# Main.net
KiCad netlist of a schematic drawn in Altium Designer
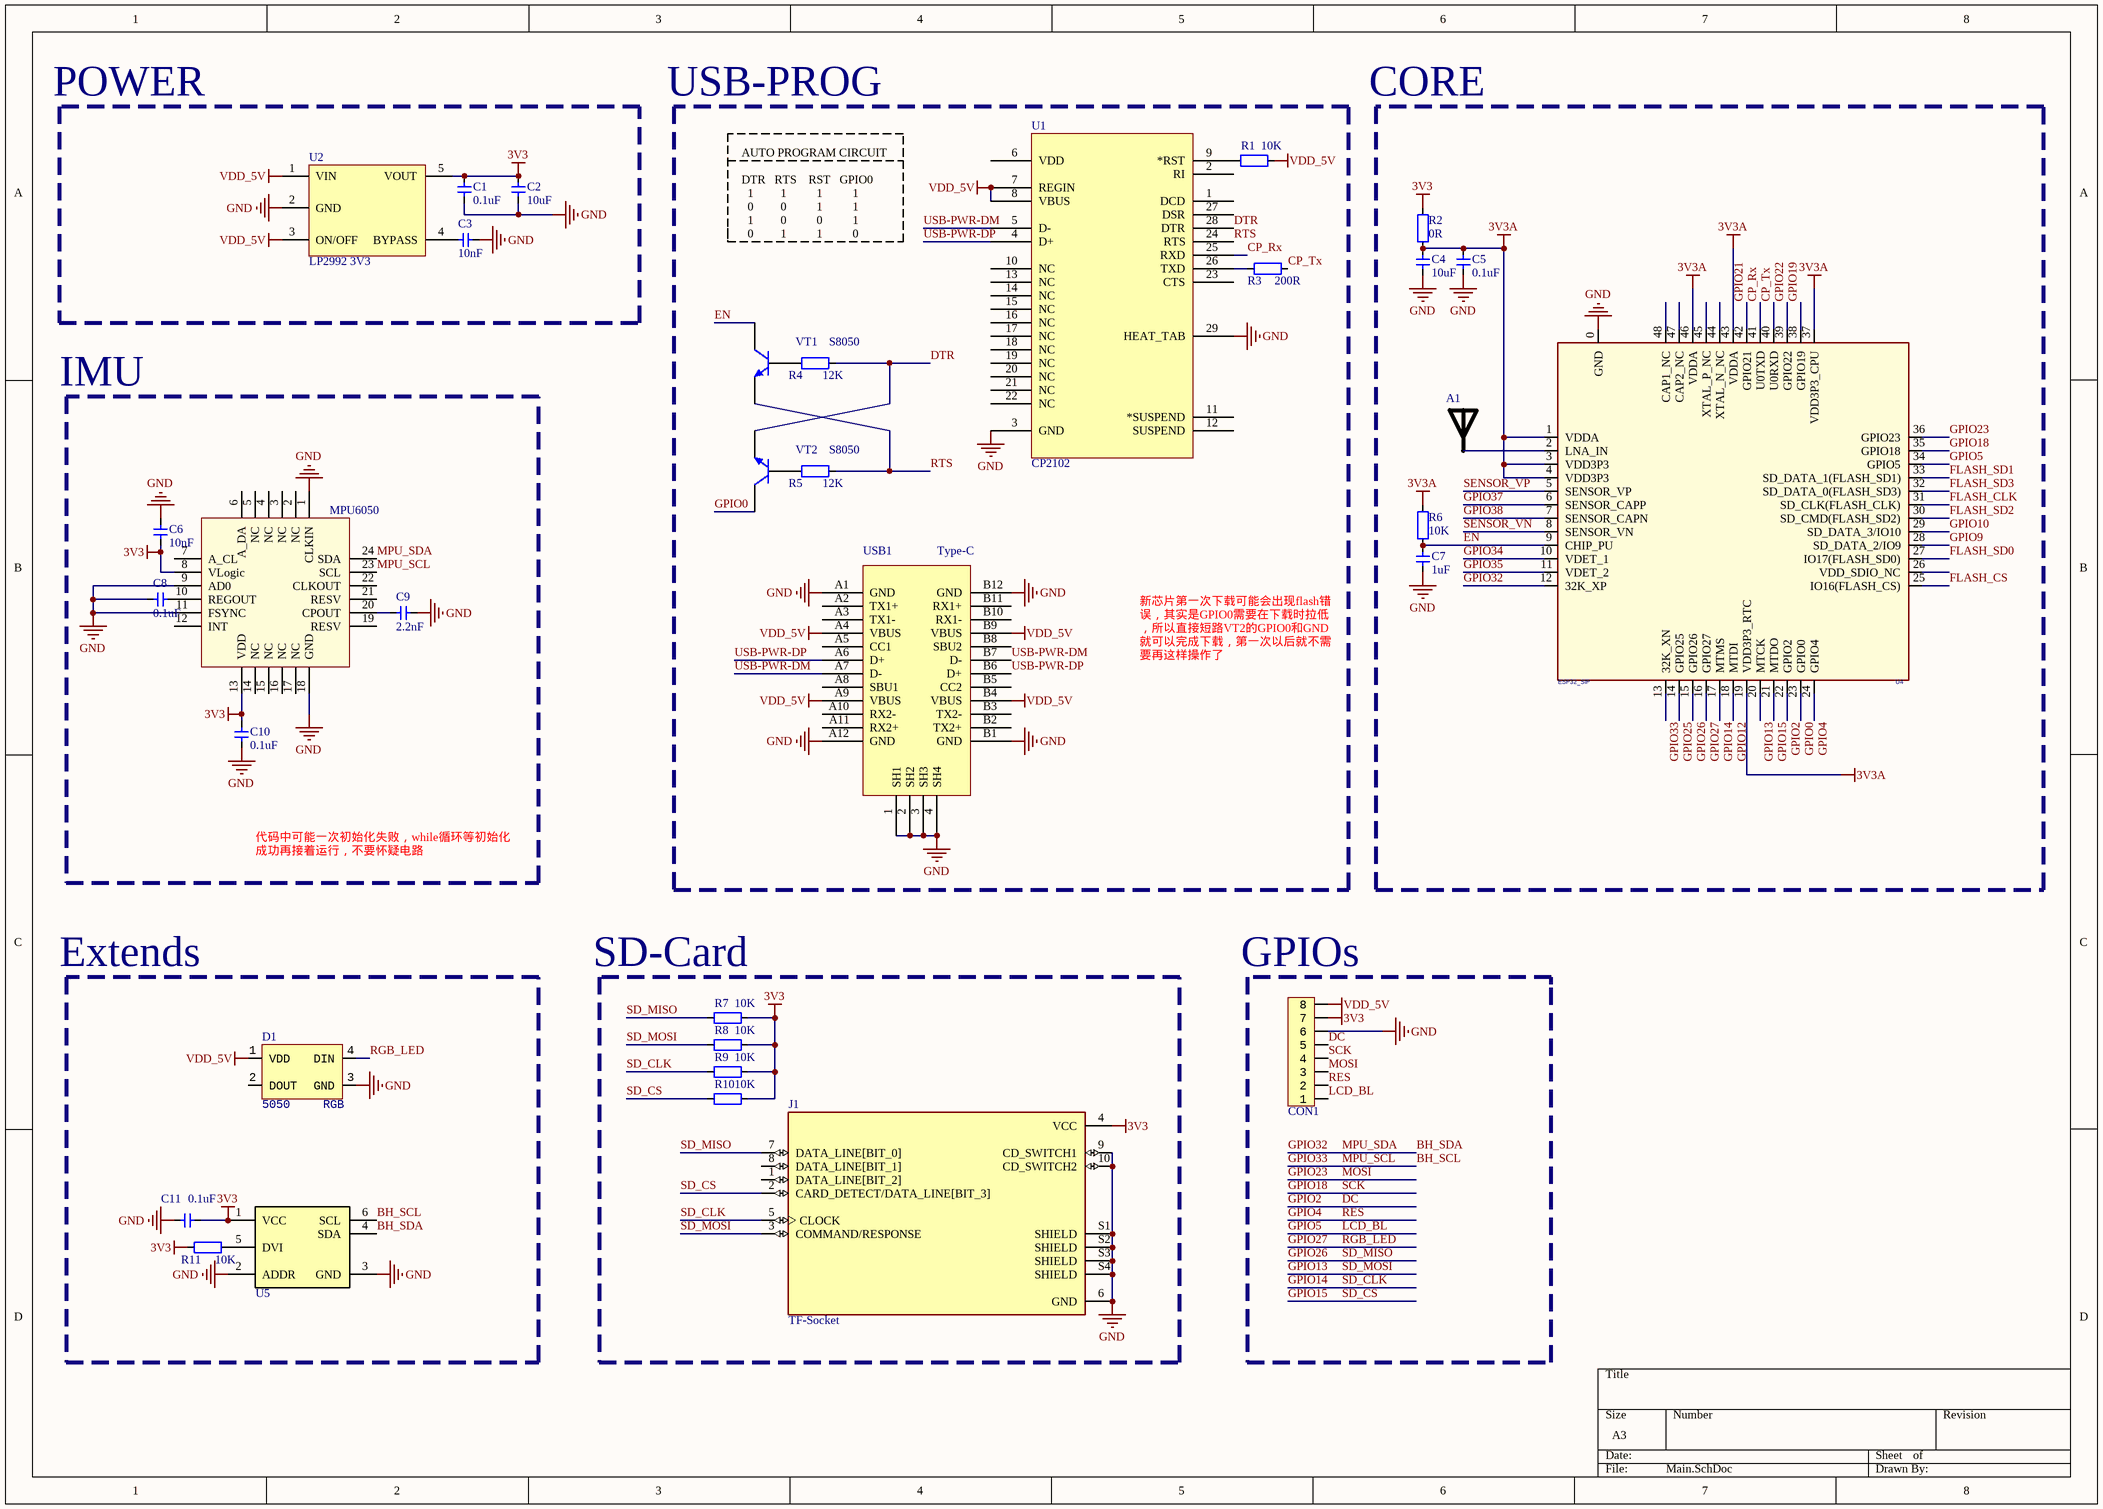
[diagram p0: Main.SchDoc]

(export (version "E")
  (design (tool "Eeschema 10.0.6"))
  (components
    (comp (ref "A1")
      (value "RAINSUN")
      (footprint "ANT-Rainsun-AN5120")
      (libsource (lib "MyPcbLib") (part "ANT-Rainsun-AP5120"))
    )
    (comp (ref "C1")
      (value "0.1uF")
      (footprint "CAP_0402")
      (description "Capacitor")
      (libsource (lib "MyPcbLib") (part "电容-0402"))
    )
    (comp (ref "C2")
      (value "10uF")
      (footprint "CAP_0402")
      (description "Capacitor")
      (libsource (lib "MyPcbLib") (part "电容-0402"))
    )
    (comp (ref "C3")
      (value "10nF")
      (footprint "CAP_0402")
      (description "Capacitor")
      (libsource (lib "MyPcbLib") (part "电容-0402"))
    )
    (comp (ref "C4")
      (value "10uF")
      (footprint "CAP_0402")
      (description "Capacitor")
      (libsource (lib "MyPcbLib") (part "电容-0402"))
    )
    (comp (ref "C5")
      (value "0.1uF")
      (footprint "CAP_0402")
      (description "Capacitor")
      (libsource (lib "MyPcbLib") (part "电容-0402"))
    )
    (comp (ref "C6")
      (value "10nF")
      (footprint "CAP_0402")
      (description "Capacitor")
      (libsource (lib "MyPcbLib") (part "电容-0402"))
    )
    (comp (ref "C7")
      (value "1uF")
      (footprint "CAP_0402")
      (description "Capacitor")
      (libsource (lib "MyPcbLib") (part "电容-0402"))
    )
    (comp (ref "C8")
      (value "0.1uF")
      (footprint "CAP_0402")
      (description "Capacitor")
      (libsource (lib "MyPcbLib") (part "电容-0402"))
    )
    (comp (ref "C9")
      (value "2.2nF")
      (footprint "CAP_0402")
      (description "Capacitor")
      (libsource (lib "MyPcbLib") (part "电容-0402"))
    )
    (comp (ref "C10")
      (value "0.1uF")
      (footprint "CAP_0402")
      (description "Capacitor")
      (libsource (lib "MyPcbLib") (part "电容-0402"))
    )
    (comp (ref "C11")
      (value "0.1uF")
      (footprint "CAP_0402")
      (description "Capacitor")
      (libsource (lib "MyPcbLib") (part "电容-0402"))
    )
    (comp (ref "CON1")
      (value "FFC_0.5_8")
      (footprint "FFC_0.5_8")
      (description "FFC")
      (libsource (lib "KitSprout") (part "FFC_0.5_8"))
    )
    (comp (ref "D1")
      (value "RGB")
      (footprint "LED_5050_WS2812B")
      (description "LED")
      (fields (field (name "TYPE") "5050"))
      (libsource (lib "KitSprout") (part "LED_5050_WS2812B"))
    )
    (comp (ref "J1")
      (value "TF-Socket")
      (footprint "TF-Card-Amphenol with TF")
      (description "10 _8 + 2_ Position Card Connector Secure Digital - microSDâ„¢ Surface Mount, Right Angle Gold")
      (fields (field (name "MP") "1140084168") (field (name "MF") "Amphenol Commercial Products"))
      (libsource (lib "MyPcbLib") (part "TF-Socket"))
    )
    (comp (ref "R1")
      (value "10K")
      (footprint "RES_0402")
      (description "Resistor")
      (libsource (lib "") (part "电阻-0402_1"))
    )
    (comp (ref "R2")
      (value "0R")
      (footprint "RES_0402")
      (description "Resistor")
      (libsource (lib "MyPcbLib") (part "电阻-0402"))
    )
    (comp (ref "R3")
      (value "200R")
      (footprint "RES_0402")
      (description "Resistor")
      (libsource (lib "") (part "电阻-0402_1"))
    )
    (comp (ref "R4")
      (value "12K")
      (footprint "RES_0402")
      (description "Resistor")
      (libsource (lib "") (part "电阻-0402_1"))
    )
    (comp (ref "R5")
      (value "12K")
      (footprint "RES_0402")
      (description "Resistor")
      (libsource (lib "") (part "电阻-0402_1"))
    )
    (comp (ref "R6")
      (value "10K")
      (footprint "RES_0402")
      (description "Resistor")
      (libsource (lib "MyPcbLib") (part "电阻-0402"))
    )
    (comp (ref "R7")
      (value "10K")
      (footprint "RES_0402")
      (description "Resistor")
      (libsource (lib "") (part "电阻-0402_1"))
    )
    (comp (ref "R8")
      (value "10K")
      (footprint "RES_0402")
      (description "Resistor")
      (libsource (lib "") (part "电阻-0402_1"))
    )
    (comp (ref "R9")
      (value "10K")
      (footprint "RES_0402")
      (description "Resistor")
      (libsource (lib "") (part "电阻-0402_1"))
    )
    (comp (ref "R10")
      (value "10K")
      (footprint "RES_0402")
      (description "Resistor")
      (libsource (lib "") (part "电阻-0402_1"))
    )
    (comp (ref "R11")
      (value "10K")
      (footprint "RES_0402")
      (description "Resistor")
      (libsource (lib "") (part "电阻-0402_1"))
    )
    (comp (ref "U1")
      (value "CP2102")
      (footprint "QFN-28")
      (description "USB转TTL")
      (libsource (lib "mLib") (part "CP2102"))
    )
    (comp (ref "U2")
      (value "LP2992 3V3")
      (footprint "SOT23-5")
      (description "LDO")
      (libsource (lib "MyPcbLib") (part "LP2992"))
    )
    (comp (ref "U3")
      (value "MPU6050")
      (footprint "QFN-24")
      (description "六轴传感器")
      (libsource (lib "mLib") (part "MPU6050"))
    )
    (comp (ref "U4")
      (value "ESP32_SIP")
      (footprint "QFN-48_7X7")
      (libsource (lib "MyPcbLib") (part "ESP32-PICO"))
    )
    (comp (ref "U5")
      (value "BH1750FVI-TR")
      (footprint "BH1750FVI")
      (libsource (lib "MyPcbLib") (part "BH1750FVI-TR"))
    )
    (comp (ref "USB1")
      (value "Type-C")
      (footprint "Type-C-TOP")
      (libsource (lib "MyPcbLib") (part "USB-Type-C-TOP"))
    )
    (comp (ref "VT1")
      (value "S8050")
      (footprint "SMT_TRIODE_NPN")
      (description "Surface mount NPN transistor, package SOT-23")
      (libsource (lib "MyPcbLib") (part "SMT_TRIODE_NPN"))
    )
    (comp (ref "VT2")
      (value "S8050")
      (footprint "SMT_TRIODE_NPN")
      (description "Surface mount NPN transistor, package SOT-23")
      (libsource (lib "MyPcbLib") (part "SMT_TRIODE_NPN"))
    )
  )
  (nets
    (net (code "1") (name "/BH_SCL") (class "Default")
      (node (ref "U3") (pin "23") (pinfunction "SCL_23") (pintype "passive"))
      (node (ref "U4") (pin "13") (pinfunction "32K_XN_13") (pintype "passive"))
      (node (ref "U5") (pin "6") (pinfunction "SCL_6") (pintype "passive"))
    )
    (net (code "2") (name "/BH_SDA") (class "Default")
      (node (ref "U3") (pin "24") (pinfunction "SDA_24") (pintype "passive"))
      (node (ref "U4") (pin "12") (pinfunction "32K_XP_12") (pintype "passive"))
      (node (ref "U5") (pin "4") (pinfunction "SDA_4") (pintype "passive"))
    )
    (net (code "3") (name "/CP_Rx") (class "Default")
      (node (ref "U1") (pin "25") (pinfunction "RXD_25") (pintype "passive"))
      (node (ref "U4") (pin "41") (pinfunction "U0TXD_41") (pintype "power_in"))
    )
    (net (code "4") (name "/CP_Tx") (class "Default")
      (node (ref "R3") (pin "1") (pinfunction "1_1") (pintype "passive"))
      (node (ref "U4") (pin "40") (pinfunction "U0RXD_40") (pintype "power_in"))
    )
    (net (code "5") (name "/DC") (class "Default")
      (node (ref "CON1") (pin "5") (pinfunction "5_5") (pintype "passive"))
      (node (ref "U4") (pin "22") (pinfunction "GPIO2_22") (pintype "passive"))
    )
    (net (code "6") (name "/DTR") (class "Default")
      (node (ref "R4") (pin "1") (pinfunction "1_1") (pintype "passive"))
      (node (ref "U1") (pin "28") (pinfunction "DTR_28") (pintype "passive"))
      (node (ref "VT2") (pin "2") (pinfunction "E_2") (pintype "passive"))
    )
    (net (code "7") (name "/EN") (class "Default")
      (node (ref "C7") (pin "1") (pinfunction "1_1") (pintype "passive"))
      (node (ref "R6") (pin "2") (pinfunction "2_2") (pintype "passive"))
      (node (ref "U4") (pin "9") (pinfunction "CHIP_PU_9") (pintype "passive"))
      (node (ref "VT1") (pin "3") (pinfunction "C_3") (pintype "passive"))
    )
    (net (code "8") (name "/FLASH_CLK") (class "Default")
      (node (ref "U4") (pin "31") (pinfunction "SD_CLK(FLASH_CLK)_31") (pintype "passive"))
    )
    (net (code "9") (name "/FLASH_CS") (class "Default")
      (node (ref "U4") (pin "25") (pinfunction "IO16(FLASH_CS)_25") (pintype "passive"))
    )
    (net (code "10") (name "/FLASH_SD0") (class "Default")
      (node (ref "U4") (pin "27") (pinfunction "IO17(FLASH_SD0)_27") (pintype "passive"))
    )
    (net (code "11") (name "/FLASH_SD1") (class "Default")
      (node (ref "U4") (pin "33") (pinfunction "SD_DATA_1(FLASH_SD1)_33") (pintype "passive"))
    )
    (net (code "12") (name "/FLASH_SD2") (class "Default")
      (node (ref "U4") (pin "30") (pinfunction "SD_CMD(FLASH_SD2)_30") (pintype "passive"))
    )
    (net (code "13") (name "/FLASH_SD3") (class "Default")
      (node (ref "U4") (pin "32") (pinfunction "SD_DATA_0(FLASH_SD3)_32") (pintype "passive"))
    )
    (net (code "14") (name "/GPIO0") (class "Default")
      (node (ref "U4") (pin "23") (pinfunction "GPIO0_23") (pintype "passive"))
      (node (ref "VT2") (pin "3") (pinfunction "C_3") (pintype "passive"))
    )
    (net (code "15") (name "/GPIO4") (class "Default")
      (node (ref "CON1") (pin "2") (pinfunction "2_2") (pintype "passive"))
      (node (ref "U4") (pin "24") (pinfunction "GPIO4_24") (pintype "passive"))
    )
    (net (code "16") (name "/GPIO5") (class "Default")
      (node (ref "CON1") (pin "1") (pinfunction "1_1") (pintype "passive"))
      (node (ref "U4") (pin "34") (pinfunction "GPIO5_34") (pintype "passive"))
    )
    (net (code "17") (name "/GPIO9") (class "Default")
      (node (ref "U4") (pin "28") (pinfunction "SD_DATA_2/IO9_28") (pintype "passive"))
    )
    (net (code "18") (name "/GPIO10") (class "Default")
      (node (ref "U4") (pin "29") (pinfunction "SD_DATA_3/IO10_29") (pintype "passive"))
    )
    (net (code "19") (name "/GPIO12") (class "Default")
      (node (ref "U4") (pin "18") (pinfunction "MTDI_18") (pintype "passive"))
    )
    (net (code "20") (name "/GPIO13") (class "Default")
      (node (ref "J1") (pin "3") (pinfunction "COMMAND/RESPONSE_3") (pintype "bidirectional"))
      (node (ref "R8") (pin "2") (pinfunction "2_2") (pintype "passive"))
      (node (ref "U4") (pin "20") (pinfunction "MTCK_20") (pintype "passive"))
    )
    (net (code "21") (name "/GPIO14") (class "Default")
      (node (ref "J1") (pin "5") (pinfunction "CLOCK_5") (pintype "bidirectional"))
      (node (ref "R9") (pin "2") (pinfunction "2_2") (pintype "passive"))
      (node (ref "U4") (pin "17") (pinfunction "MTMS_17") (pintype "passive"))
    )
    (net (code "22") (name "/GPIO15") (class "Default")
      (node (ref "J1") (pin "2") (pinfunction "CARD_DETECT/DATA_LINE[BIT_3]_2") (pintype "bidirectional"))
      (node (ref "R10") (pin "2") (pinfunction "2_2") (pintype "passive"))
      (node (ref "U4") (pin "21") (pinfunction "MTDO_21") (pintype "passive"))
    )
    (net (code "23") (name "/GPIO18") (class "Default")
      (node (ref "CON1") (pin "4") (pinfunction "4_4") (pintype "passive"))
      (node (ref "U4") (pin "35") (pinfunction "GPIO18_35") (pintype "passive"))
    )
    (net (code "24") (name "/GPIO19") (class "Default")
      (node (ref "U4") (pin "38") (pinfunction "GPIO19_38") (pintype "passive"))
    )
    (net (code "25") (name "/GPIO21") (class "Default")
      (node (ref "U4") (pin "42") (pinfunction "GPIO21_42") (pintype "passive"))
    )
    (net (code "26") (name "/GPIO22") (class "Default")
      (node (ref "U4") (pin "39") (pinfunction "GPIO22_39") (pintype "passive"))
    )
    (net (code "27") (name "/GPIO23") (class "Default")
      (node (ref "CON1") (pin "3") (pinfunction "3_3") (pintype "passive"))
      (node (ref "U4") (pin "36") (pinfunction "GPIO23_36") (pintype "passive"))
    )
    (net (code "28") (name "/GPIO25") (class "Default")
      (node (ref "U4") (pin "14") (pinfunction "GPIO25_14") (pintype "passive"))
    )
    (net (code "29") (name "/GPIO26") (class "Default")
      (node (ref "J1") (pin "7") (pinfunction "DATA_LINE[BIT_0]_7") (pintype "bidirectional"))
      (node (ref "R7") (pin "2") (pinfunction "2_2") (pintype "passive"))
      (node (ref "U4") (pin "15") (pinfunction "GPIO26_15") (pintype "passive"))
    )
    (net (code "30") (name "/GPIO27") (class "Default")
      (node (ref "D1") (pin "4") (pinfunction "DIN_4") (pintype "passive"))
      (node (ref "U4") (pin "16") (pinfunction "GPIO27_16") (pintype "passive"))
    )
    (net (code "31") (name "/GPIO34") (class "Default")
      (node (ref "U4") (pin "10") (pinfunction "VDET_1_10") (pintype "passive"))
    )
    (net (code "32") (name "/GPIO35") (class "Default")
      (node (ref "U4") (pin "11") (pinfunction "VDET_2_11") (pintype "passive"))
    )
    (net (code "33") (name "/GPIO37") (class "Default")
      (node (ref "U4") (pin "6") (pinfunction "SENSOR_CAPP_6") (pintype "passive"))
    )
    (net (code "34") (name "/GPIO38") (class "Default")
      (node (ref "U4") (pin "7") (pinfunction "SENSOR_CAPN_7") (pintype "passive"))
    )
    (net (code "35") (name "/RTS") (class "Default")
      (node (ref "R5") (pin "1") (pinfunction "1_1") (pintype "passive"))
      (node (ref "U1") (pin "24") (pinfunction "RTS_24") (pintype "passive"))
      (node (ref "VT1") (pin "2") (pinfunction "E_2") (pintype "passive"))
    )
    (net (code "36") (name "/SENSOR_VN") (class "Default")
      (node (ref "U4") (pin "8") (pinfunction "SENSOR_VN_8") (pintype "passive"))
    )
    (net (code "37") (name "/SENSOR_VP") (class "Default")
      (node (ref "U4") (pin "5") (pinfunction "SENSOR_VP_5") (pintype "passive"))
    )
    (net (code "38") (name "/USB-PWR-DM") (class "Default")
      (node (ref "U1") (pin "5") (pinfunction "D-_5") (pintype "passive"))
      (node (ref "USB1") (pin "A7") (pinfunction "D-_A7") (pintype "passive"))
      (node (ref "USB1") (pin "B7") (pinfunction "D-_B7") (pintype "passive"))
    )
    (net (code "39") (name "/USB-PWR-DP") (class "Default")
      (node (ref "U1") (pin "4") (pinfunction "D+_4") (pintype "passive"))
      (node (ref "USB1") (pin "A6") (pinfunction "D+_A6") (pintype "passive"))
      (node (ref "USB1") (pin "B6") (pinfunction "D+_B6") (pintype "passive"))
    )
    (net (code "40") (name "3V3") (class "Default")
      (node (ref "C1") (pin "2") (pinfunction "2_2") (pintype "passive"))
      (node (ref "C10") (pin "2") (pinfunction "2_2") (pintype "passive"))
      (node (ref "C11") (pin "1") (pinfunction "1_1") (pintype "passive"))
      (node (ref "C2") (pin "2") (pinfunction "2_2") (pintype "passive"))
      (node (ref "C6") (pin "1") (pinfunction "1_1") (pintype "passive"))
      (node (ref "CON1") (pin "7") (pinfunction "7_7") (pintype "passive"))
      (node (ref "J1") (pin "4") (pinfunction "VCC_4") (pintype "power_in"))
      (node (ref "R10") (pin "1") (pinfunction "1_1") (pintype "passive"))
      (node (ref "R11") (pin "2") (pinfunction "2_2") (pintype "passive"))
      (node (ref "R2") (pin "1") (pinfunction "1_1") (pintype "passive"))
      (node (ref "R7") (pin "1") (pinfunction "1_1") (pintype "passive"))
      (node (ref "R8") (pin "1") (pinfunction "1_1") (pintype "passive"))
      (node (ref "R9") (pin "1") (pinfunction "1_1") (pintype "passive"))
      (node (ref "U2") (pin "5") (pinfunction "VOUT_5") (pintype "passive"))
      (node (ref "U3") (pin "13") (pinfunction "VDD_13") (pintype "passive"))
      (node (ref "U3") (pin "8") (pinfunction "VLogic_8") (pintype "passive"))
      (node (ref "U5") (pin "1") (pinfunction "VCC_1") (pintype "passive"))
    )
    (net (code "41") (name "3V3A") (class "Default")
      (node (ref "C4") (pin "2") (pinfunction "2_2") (pintype "passive"))
      (node (ref "C5") (pin "2") (pinfunction "2_2") (pintype "passive"))
      (node (ref "R2") (pin "2") (pinfunction "2_2") (pintype "passive"))
      (node (ref "R6") (pin "1") (pinfunction "1_1") (pintype "passive"))
      (node (ref "U4") (pin "1") (pinfunction "VDDA_1") (pintype "power_in"))
      (node (ref "U4") (pin "19") (pinfunction "VDD3P3_RTC_19") (pintype "power_in"))
      (node (ref "U4") (pin "3") (pinfunction "VDD3P3_3") (pintype "power_in"))
      (node (ref "U4") (pin "37") (pinfunction "VDD3P3_CPU_37") (pintype "power_in"))
      (node (ref "U4") (pin "4") (pinfunction "VDD3P3_4") (pintype "power_in"))
      (node (ref "U4") (pin "43") (pinfunction "VDDA_43") (pintype "power_in"))
      (node (ref "U4") (pin "46") (pinfunction "VDDA_46") (pintype "power_in"))
    )
    (net (code "42") (name "GND") (class "Default")
      (node (ref "C1") (pin "1") (pinfunction "1_1") (pintype "passive"))
      (node (ref "C10") (pin "1") (pinfunction "1_1") (pintype "passive"))
      (node (ref "C11") (pin "2") (pinfunction "2_2") (pintype "passive"))
      (node (ref "C2") (pin "1") (pinfunction "1_1") (pintype "passive"))
      (node (ref "C3") (pin "1") (pinfunction "1_1") (pintype "passive"))
      (node (ref "C4") (pin "1") (pinfunction "1_1") (pintype "passive"))
      (node (ref "C5") (pin "1") (pinfunction "1_1") (pintype "passive"))
      (node (ref "C6") (pin "2") (pinfunction "2_2") (pintype "passive"))
      (node (ref "C7") (pin "2") (pinfunction "2_2") (pintype "passive"))
      (node (ref "C8") (pin "2") (pinfunction "2_2") (pintype "passive"))
      (node (ref "C9") (pin "1") (pinfunction "1_1") (pintype "passive"))
      (node (ref "CON1") (pin "6") (pinfunction "6_6") (pintype "passive"))
      (node (ref "D1") (pin "3") (pinfunction "GND_3") (pintype "passive"))
      (node (ref "J1") (pin "10") (pinfunction "CD_SWITCH2_10") (pintype "bidirectional"))
      (node (ref "J1") (pin "6") (pinfunction "GND_6") (pintype "power_in"))
      (node (ref "J1") (pin "9") (pinfunction "CD_SWITCH1_9") (pintype "bidirectional"))
      (node (ref "J1") (pin "S1") (pinfunction "SHIELD_S1") (pintype "passive"))
      (node (ref "J1") (pin "S2") (pinfunction "SHIELD_S2") (pintype "passive"))
      (node (ref "J1") (pin "S3") (pinfunction "SHIELD_S3") (pintype "passive"))
      (node (ref "J1") (pin "S4") (pinfunction "SHIELD_S4") (pintype "passive"))
      (node (ref "U1") (pin "29") (pinfunction "HEAT_TAB_29") (pintype "passive"))
      (node (ref "U1") (pin "3") (pinfunction "GND_3") (pintype "passive"))
      (node (ref "U2") (pin "2") (pinfunction "GND_2") (pintype "passive"))
      (node (ref "U3") (pin "1") (pinfunction "CLKIN_1") (pintype "passive"))
      (node (ref "U3") (pin "11") (pinfunction "FSYNC_11") (pintype "passive"))
      (node (ref "U3") (pin "18") (pinfunction "GND_18") (pintype "passive"))
      (node (ref "U3") (pin "9") (pinfunction "AD0_9") (pintype "passive"))
      (node (ref "U4") (pin "0") (pinfunction "GND_0") (pintype "power_in"))
      (node (ref "U5") (pin "2") (pinfunction "ADDR_2") (pintype "passive"))
      (node (ref "U5") (pin "3") (pinfunction "GND_3") (pintype "passive"))
      (node (ref "USB1") (pin "1") (pinfunction "SH1_1") (pintype "passive"))
      (node (ref "USB1") (pin "2") (pinfunction "SH2_2") (pintype "passive"))
      (node (ref "USB1") (pin "3") (pinfunction "SH3_3") (pintype "passive"))
      (node (ref "USB1") (pin "4") (pinfunction "SH4_4") (pintype "passive"))
      (node (ref "USB1") (pin "A1") (pinfunction "GND_A1") (pintype "passive"))
      (node (ref "USB1") (pin "A12") (pinfunction "GND_A12") (pintype "passive"))
      (node (ref "USB1") (pin "B1") (pinfunction "GND_B1") (pintype "passive"))
      (node (ref "USB1") (pin "B12") (pinfunction "GND_B12") (pintype "passive"))
    )
    (net (code "43") (name "Net-(U1-*RST)") (class "Default")
      (node (ref "R1") (pin "2") (pinfunction "2_2") (pintype "passive"))
      (node (ref "U1") (pin "9") (pinfunction "*RST_9") (pintype "passive"))
    )
    (net (code "44") (name "Net-(U1-TXD)") (class "Default")
      (node (ref "R3") (pin "2") (pinfunction "2_2") (pintype "passive"))
      (node (ref "U1") (pin "26") (pinfunction "TXD_26") (pintype "passive"))
    )
    (net (code "45") (name "Net-(U2-BYPASS)") (class "Default")
      (node (ref "C3") (pin "2") (pinfunction "2_2") (pintype "passive"))
      (node (ref "U2") (pin "4") (pinfunction "BYPASS_4") (pintype "passive"))
    )
    (net (code "46") (name "Net-(U3-CPOUT)") (class "Default")
      (node (ref "C9") (pin "2") (pinfunction "2_2") (pintype "passive"))
      (node (ref "U3") (pin "20") (pinfunction "CPOUT_20") (pintype "passive"))
    )
    (net (code "47") (name "Net-(U3-REGOUT)") (class "Default")
      (node (ref "C8") (pin "1") (pinfunction "1_1") (pintype "passive"))
      (node (ref "U3") (pin "10") (pinfunction "REGOUT_10") (pintype "passive"))
    )
    (net (code "48") (name "Net-(U4-LNA_IN)") (class "Default")
      (node (ref "A1") (pin "1") (pinfunction "1_1") (pintype "passive"))
      (node (ref "U4") (pin "2") (pinfunction "LNA_IN_2") (pintype "passive"))
    )
    (net (code "49") (name "Net-(U5-DVI)") (class "Default")
      (node (ref "R11") (pin "1") (pinfunction "1_1") (pintype "passive"))
      (node (ref "U5") (pin "5") (pinfunction "DVI_5") (pintype "passive"))
    )
    (net (code "50") (name "Net-(VT1-B)") (class "Default")
      (node (ref "R4") (pin "2") (pinfunction "2_2") (pintype "passive"))
      (node (ref "VT1") (pin "1") (pinfunction "B_1") (pintype "passive"))
    )
    (net (code "51") (name "Net-(VT2-B)") (class "Default")
      (node (ref "R5") (pin "2") (pinfunction "2_2") (pintype "passive"))
      (node (ref "VT2") (pin "1") (pinfunction "B_1") (pintype "passive"))
    )
    (net (code "52") (name "VDD_5V") (class "Default")
      (node (ref "CON1") (pin "8") (pinfunction "8_8") (pintype "passive"))
      (node (ref "D1") (pin "1") (pinfunction "VDD_1") (pintype "passive"))
      (node (ref "R1") (pin "1") (pinfunction "1_1") (pintype "passive"))
      (node (ref "U1") (pin "7") (pinfunction "REGIN_7") (pintype "passive"))
      (node (ref "U1") (pin "8") (pinfunction "VBUS_8") (pintype "passive"))
      (node (ref "U2") (pin "1") (pinfunction "VIN_1") (pintype "passive"))
      (node (ref "U2") (pin "3") (pinfunction "ON/OFF_3") (pintype "passive"))
      (node (ref "USB1") (pin "A4") (pinfunction "VBUS_A4") (pintype "passive"))
      (node (ref "USB1") (pin "A9") (pinfunction "VBUS_A9") (pintype "passive"))
      (node (ref "USB1") (pin "B4") (pinfunction "VBUS_B4") (pintype "passive"))
      (node (ref "USB1") (pin "B9") (pinfunction "VBUS_B9") (pintype "passive"))
    )
    (net (code "53") (name "unconnected-(D1-DOUT-Pad2)") (class "Default")
      (node (ref "D1") (pin "2") (pinfunction "DOUT_2") (pintype "passive"))
    )
    (net (code "54") (name "unconnected-(J1-DATA_LINE[BIT_1]-Pad8)") (class "Default")
      (node (ref "J1") (pin "8") (pinfunction "DATA_LINE[BIT_1]_8") (pintype "bidirectional"))
    )
    (net (code "55") (name "unconnected-(J1-DATA_LINE[BIT_2]-Pad1)") (class "Default")
      (node (ref "J1") (pin "1") (pinfunction "DATA_LINE[BIT_2]_1") (pintype "bidirectional"))
    )
    (net (code "56") (name "unconnected-(U1-*SUSPEND-Pad11)") (class "Default")
      (node (ref "U1") (pin "11") (pinfunction "*SUSPEND_11") (pintype "passive"))
    )
    (net (code "57") (name "unconnected-(U1-CTS-Pad23)") (class "Default")
      (node (ref "U1") (pin "23") (pinfunction "CTS_23") (pintype "passive"))
    )
    (net (code "58") (name "unconnected-(U1-DCD-Pad1)") (class "Default")
      (node (ref "U1") (pin "1") (pinfunction "DCD_1") (pintype "passive"))
    )
    (net (code "59") (name "unconnected-(U1-DSR-Pad27)") (class "Default")
      (node (ref "U1") (pin "27") (pinfunction "DSR_27") (pintype "passive"))
    )
    (net (code "60") (name "unconnected-(U1-NC-Pad10)") (class "Default")
      (node (ref "U1") (pin "10") (pinfunction "NC_10") (pintype "passive"))
    )
    (net (code "61") (name "unconnected-(U1-NC-Pad13)") (class "Default")
      (node (ref "U1") (pin "13") (pinfunction "NC_13") (pintype "passive"))
    )
    (net (code "62") (name "unconnected-(U1-NC-Pad14)") (class "Default")
      (node (ref "U1") (pin "14") (pinfunction "NC_14") (pintype "passive"))
    )
    (net (code "63") (name "unconnected-(U1-NC-Pad15)") (class "Default")
      (node (ref "U1") (pin "15") (pinfunction "NC_15") (pintype "passive"))
    )
    (net (code "64") (name "unconnected-(U1-NC-Pad16)") (class "Default")
      (node (ref "U1") (pin "16") (pinfunction "NC_16") (pintype "passive"))
    )
    (net (code "65") (name "unconnected-(U1-NC-Pad17)") (class "Default")
      (node (ref "U1") (pin "17") (pinfunction "NC_17") (pintype "passive"))
    )
    (net (code "66") (name "unconnected-(U1-NC-Pad18)") (class "Default")
      (node (ref "U1") (pin "18") (pinfunction "NC_18") (pintype "passive"))
    )
    (net (code "67") (name "unconnected-(U1-NC-Pad19)") (class "Default")
      (node (ref "U1") (pin "19") (pinfunction "NC_19") (pintype "passive"))
    )
    (net (code "68") (name "unconnected-(U1-NC-Pad20)") (class "Default")
      (node (ref "U1") (pin "20") (pinfunction "NC_20") (pintype "passive"))
    )
    (net (code "69") (name "unconnected-(U1-NC-Pad21)") (class "Default")
      (node (ref "U1") (pin "21") (pinfunction "NC_21") (pintype "passive"))
    )
    (net (code "70") (name "unconnected-(U1-NC-Pad22)") (class "Default")
      (node (ref "U1") (pin "22") (pinfunction "NC_22") (pintype "passive"))
    )
    (net (code "71") (name "unconnected-(U1-RI-Pad2)") (class "Default")
      (node (ref "U1") (pin "2") (pinfunction "RI_2") (pintype "passive"))
    )
    (net (code "72") (name "unconnected-(U1-SUSPEND-Pad12)") (class "Default")
      (node (ref "U1") (pin "12") (pinfunction "SUSPEND_12") (pintype "passive"))
    )
    (net (code "73") (name "unconnected-(U1-VDD-Pad6)") (class "Default")
      (node (ref "U1") (pin "6") (pinfunction "VDD_6") (pintype "passive"))
    )
    (net (code "74") (name "unconnected-(U3-A_CL-Pad7)") (class "Default")
      (node (ref "U3") (pin "7") (pinfunction "A_CL_7") (pintype "passive"))
    )
    (net (code "75") (name "unconnected-(U3-A_DA-Pad6)") (class "Default")
      (node (ref "U3") (pin "6") (pinfunction "A_DA_6") (pintype "passive"))
    )
    (net (code "76") (name "unconnected-(U3-CLKOUT-Pad22)") (class "Default")
      (node (ref "U3") (pin "22") (pinfunction "CLKOUT_22") (pintype "passive"))
    )
    (net (code "77") (name "unconnected-(U3-INT-Pad12)") (class "Default")
      (node (ref "U3") (pin "12") (pinfunction "INT_12") (pintype "passive"))
    )
    (net (code "78") (name "unconnected-(U3-NC-Pad2)") (class "Default")
      (node (ref "U3") (pin "2") (pinfunction "NC_2") (pintype "passive"))
    )
    (net (code "79") (name "unconnected-(U3-NC-Pad3)") (class "Default")
      (node (ref "U3") (pin "3") (pinfunction "NC_3") (pintype "passive"))
    )
    (net (code "80") (name "unconnected-(U3-NC-Pad4)") (class "Default")
      (node (ref "U3") (pin "4") (pinfunction "NC_4") (pintype "passive"))
    )
    (net (code "81") (name "unconnected-(U3-NC-Pad5)") (class "Default")
      (node (ref "U3") (pin "5") (pinfunction "NC_5") (pintype "passive"))
    )
    (net (code "82") (name "unconnected-(U3-NC-Pad14)") (class "Default")
      (node (ref "U3") (pin "14") (pinfunction "NC_14") (pintype "passive"))
    )
    (net (code "83") (name "unconnected-(U3-NC-Pad15)") (class "Default")
      (node (ref "U3") (pin "15") (pinfunction "NC_15") (pintype "passive"))
    )
    (net (code "84") (name "unconnected-(U3-NC-Pad16)") (class "Default")
      (node (ref "U3") (pin "16") (pinfunction "NC_16") (pintype "passive"))
    )
    (net (code "85") (name "unconnected-(U3-NC-Pad17)") (class "Default")
      (node (ref "U3") (pin "17") (pinfunction "NC_17") (pintype "passive"))
    )
    (net (code "86") (name "unconnected-(U3-RESV-Pad19)") (class "Default")
      (node (ref "U3") (pin "19") (pinfunction "RESV_19") (pintype "passive"))
    )
    (net (code "87") (name "unconnected-(U3-RESV-Pad21)") (class "Default")
      (node (ref "U3") (pin "21") (pinfunction "RESV_21") (pintype "passive"))
    )
    (net (code "88") (name "unconnected-(U4-CAP1_NC-Pad48)") (class "Default")
      (node (ref "U4") (pin "48") (pinfunction "CAP1_NC_48") (pintype "passive"))
    )
    (net (code "89") (name "unconnected-(U4-CAP2_NC-Pad47)") (class "Default")
      (node (ref "U4") (pin "47") (pinfunction "CAP2_NC_47") (pintype "passive"))
    )
    (net (code "90") (name "unconnected-(U4-VDD_SDIO_NC-Pad26)") (class "Default")
      (node (ref "U4") (pin "26") (pinfunction "VDD_SDIO_NC_26") (pintype "passive"))
    )
    (net (code "91") (name "unconnected-(U4-XTAL_N_NC-Pad44)") (class "Default")
      (node (ref "U4") (pin "44") (pinfunction "XTAL_N_NC_44") (pintype "passive"))
    )
    (net (code "92") (name "unconnected-(U4-XTAL_P_NC-Pad45)") (class "Default")
      (node (ref "U4") (pin "45") (pinfunction "XTAL_P_NC_45") (pintype "passive"))
    )
    (net (code "93") (name "unconnected-(USB1-CC1-PadA5)") (class "Default")
      (node (ref "USB1") (pin "A5") (pinfunction "CC1_A5") (pintype "passive"))
    )
    (net (code "94") (name "unconnected-(USB1-CC2-PadB5)") (class "Default")
      (node (ref "USB1") (pin "B5") (pinfunction "CC2_B5") (pintype "passive"))
    )
    (net (code "95") (name "unconnected-(USB1-RX1+-PadB11)") (class "Default")
      (node (ref "USB1") (pin "B11") (pinfunction "RX1+_B11") (pintype "passive"))
    )
    (net (code "96") (name "unconnected-(USB1-RX1--PadB10)") (class "Default")
      (node (ref "USB1") (pin "B10") (pinfunction "RX1-_B10") (pintype "passive"))
    )
    (net (code "97") (name "unconnected-(USB1-RX2+-PadA11)") (class "Default")
      (node (ref "USB1") (pin "A11") (pinfunction "RX2+_A11") (pintype "passive"))
    )
    (net (code "98") (name "unconnected-(USB1-RX2--PadA10)") (class "Default")
      (node (ref "USB1") (pin "A10") (pinfunction "RX2-_A10") (pintype "passive"))
    )
    (net (code "99") (name "unconnected-(USB1-SBU1-PadA8)") (class "Default")
      (node (ref "USB1") (pin "A8") (pinfunction "SBU1_A8") (pintype "passive"))
    )
    (net (code "100") (name "unconnected-(USB1-SBU2-PadB8)") (class "Default")
      (node (ref "USB1") (pin "B8") (pinfunction "SBU2_B8") (pintype "passive"))
    )
    (net (code "101") (name "unconnected-(USB1-TX1+-PadA2)") (class "Default")
      (node (ref "USB1") (pin "A2") (pinfunction "TX1+_A2") (pintype "passive"))
    )
    (net (code "102") (name "unconnected-(USB1-TX1--PadA3)") (class "Default")
      (node (ref "USB1") (pin "A3") (pinfunction "TX1-_A3") (pintype "passive"))
    )
    (net (code "103") (name "unconnected-(USB1-TX2+-PadB2)") (class "Default")
      (node (ref "USB1") (pin "B2") (pinfunction "TX2+_B2") (pintype "passive"))
    )
    (net (code "104") (name "unconnected-(USB1-TX2--PadB3)") (class "Default")
      (node (ref "USB1") (pin "B3") (pinfunction "TX2-_B3") (pintype "passive"))
    )
  )
)
